# MainPowerSupply.net
KiCad netlist of a schematic drawn in Altium Designer
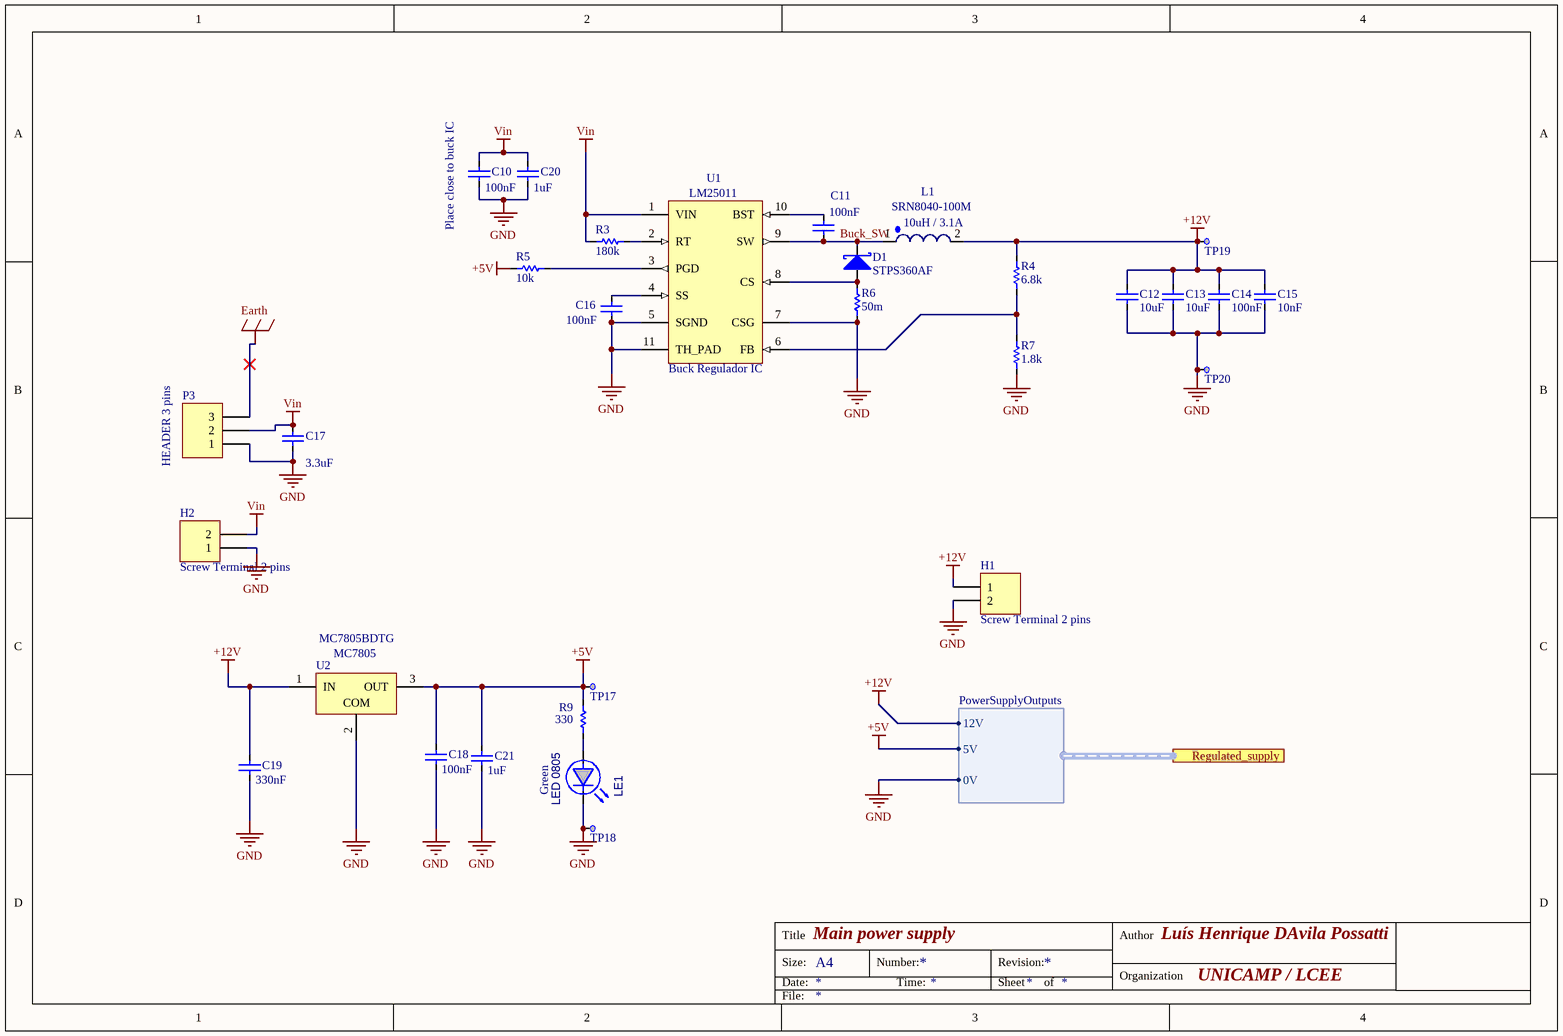
[diagram p0: MainPowerSupply.SchDoc]

(export (version "E")
  (design (tool "Eeschema 10.0.6"))
  (components
    (comp (ref "C10")
      (value "Place close to buck IC")
      (footprint "Capacitor 0805")
      (description "SMD ceramic capacitor 0805")
      (fields (field (name "ALTIUM_VALUE") "100nF"))
      (libsource (lib "EdgeInverter_library") (part "Capacitor 0805"))
    )
    (comp (ref "C11")
      (value "100nF")
      (footprint "Capacitor 0805")
      (description "SMD ceramic capacitor 0805")
      (fields (field (name "Comment") "Capacitor 0805"))
      (libsource (lib "EdgeInverter_library") (part "Capacitor 0805"))
    )
    (comp (ref "C12")
      (value "10uF")
      (footprint "Capacitor 0805")
      (description "SMD ceramic capacitor 0805")
      (fields (field (name "Comment") "Capacitor 0805"))
      (libsource (lib "EdgeInverter_library") (part "Capacitor 0805"))
    )
    (comp (ref "C13")
      (value "10uF")
      (footprint "Capacitor 0805")
      (description "SMD ceramic capacitor 0805")
      (fields (field (name "Comment") "Capacitor 0805"))
      (libsource (lib "EdgeInverter_library") (part "Capacitor 0805"))
    )
    (comp (ref "C14")
      (value "100nF")
      (footprint "Capacitor 0805")
      (description "SMD ceramic capacitor 0805")
      (fields (field (name "Comment") "Capacitor 0805"))
      (libsource (lib "EdgeInverter_library") (part "Capacitor 0805"))
    )
    (comp (ref "C15")
      (value "10nF")
      (footprint "Capacitor 0805")
      (description "SMD ceramic capacitor 0805")
      (fields (field (name "Comment") "Capacitor 0805"))
      (libsource (lib "EdgeInverter_library") (part "Capacitor 0805"))
    )
    (comp (ref "C16")
      (value "100nF")
      (footprint "Capacitor 0805")
      (description "SMD ceramic capacitor 0805")
      (fields (field (name "Comment") "Capacitor 0805"))
      (libsource (lib "EdgeInverter_library") (part "Capacitor 0805"))
    )
    (comp (ref "C17")
      (value "3.3uF")
      (footprint "Capacitor 0805")
      (description "SMD ceramic capacitor 0805")
      (fields (field (name "Comment") "Place close to input"))
      (libsource (lib "EdgeInverter_library") (part "Capacitor 0805"))
    )
    (comp (ref "C18")
      (value "100nF")
      (footprint "Capacitor 0805")
      (description "SMD ceramic capacitor 0805")
      (fields (field (name "Comment") "Place close do MC7805"))
      (libsource (lib "EdgeInverter_library") (part "Capacitor 0805"))
    )
    (comp (ref "C19")
      (value "330nF")
      (footprint "Capacitor 0805")
      (description "SMD ceramic capacitor 0805")
      (fields (field (name "Comment") "Place close do MC7805"))
      (libsource (lib "EdgeInverter_library") (part "Capacitor 0805"))
    )
    (comp (ref "C20")
      (value "1uF")
      (footprint "Capacitor 0805")
      (description "SMD ceramic capacitor 0805")
      (fields (field (name "Comment") "Place close to buck IC"))
      (libsource (lib "EdgeInverter_library") (part "Capacitor 0805"))
    )
    (comp (ref "C21")
      (value "1uF")
      (footprint "Capacitor 0805")
      (description "SMD ceramic capacitor 0805")
      (fields (field (name "Comment") "Place close do MC7805"))
      (libsource (lib "EdgeInverter_library") (part "Capacitor 0805"))
    )
    (comp (ref "D1")
      (value "STPS360AF")
      (footprint "SOD 128")
      (description "DIODE SCHOTTKY 60V 3A SOD128")
      (libsource (lib "EdgeInverter_library") (part "STPS360AF"))
    )
    (comp (ref "H1")
      (value "Screw Terminal 2 pins")
      (footprint "OSTTA020161")
      (libsource (lib "EdgeInverter_library") (part "OSTTA020161"))
    )
    (comp (ref "H2")
      (value "Screw Terminal 2 pins")
      (footprint "OSTTA020161")
      (libsource (lib "") (part "OSTTA020161_1"))
    )
    (comp (ref "L1")
      (value "SRN8040-100M")
      (footprint "SRN8040")
      (description "Inductor 10UH 3.1A 50 mΩ SMD")
      (fields (field (name "ALTIUM_VALUE") "10uH / 3.1A"))
      (libsource (lib "EdgeInverter_library") (part "SRN8040-100M"))
    )
    (comp (ref "LE1")
      (value "LED 0805")
      (footprint "LED 0805 Green")
      (description "LEDSMD 0805")
      (fields (field (name "COLOR") "Green"))
      (libsource (lib "EdgeInverter_library") (part "LEDSMD 0805"))
    )
    (comp (ref "P3")
      (value "HEADER 3 pins")
      (footprint "HDR1X3")
      (description "Header 2.54mm 3 pins")
      (libsource (lib "EdgeInverter_library") (part "HEADER 3 pins"))
    )
    (comp (ref "R3")
      (value "180k")
      (footprint "Resistor 0805")
      (description "SMD resistor 0805")
      (fields (field (name "Comment") "Resistor 0805"))
      (libsource (lib "EdgeInverter_library") (part "Resistor 0805"))
    )
    (comp (ref "R4")
      (value "6.8k")
      (footprint "Resistor 0805")
      (description "SMD resistor 0805")
      (fields (field (name "Comment") "Resistor 0805"))
      (libsource (lib "EdgeInverter_library") (part "Resistor 0805"))
    )
    (comp (ref "R5")
      (value "10k")
      (footprint "Resistor 0805")
      (description "SMD resistor 0805")
      (fields (field (name "Comment") "Resistor 0805"))
      (libsource (lib "EdgeInverter_library") (part "Resistor 0805"))
    )
    (comp (ref "R6")
      (value "50m")
      (footprint "Resistor 0805")
      (description "RESISTOR 0.05 OHM 1% 1W SMD 1206")
      (fields (field (name "Comment") "MCS1632R050FER"))
      (libsource (lib "EdgeInverter_library") (part "MCS1632R050FER"))
    )
    (comp (ref "R7")
      (value "1.8k")
      (footprint "Resistor 0805")
      (description "SMD resistor 0805")
      (fields (field (name "Comment") "Resistor 0805"))
      (libsource (lib "EdgeInverter_library") (part "Resistor 0805"))
    )
    (comp (ref "R9")
      (value "330")
      (footprint "Resistor 0805")
      (description "SMD resistor 0805")
      (fields (field (name "Comment") "Resistor 0805"))
      (libsource (lib "EdgeInverter_library") (part "Resistor 0805"))
    )
    (comp (ref "TP17")
      (value "Name of signal")
      (footprint "Test point")
      (description "Test point to probe with oscilloscope")
      (libsource (lib "EdgeInverter_library") (part "Test point"))
    )
    (comp (ref "TP18")
      (value "Name of signal")
      (footprint "Test point")
      (description "Test point to probe with oscilloscope")
      (libsource (lib "EdgeInverter_library") (part "Test point"))
    )
    (comp (ref "TP19")
      (value "Name of signal")
      (footprint "Test point")
      (description "Test point to probe with oscilloscope")
      (libsource (lib "EdgeInverter_library") (part "Test point"))
    )
    (comp (ref "TP20")
      (value "Name of signal")
      (footprint "Test point")
      (description "Test point to probe with oscilloscope")
      (libsource (lib "EdgeInverter_library") (part "Test point"))
    )
    (comp (ref "U1")
      (value "Buck Regulador IC")
      (footprint "HVSSOP 10")
      (description "IC REG BUCK ADJ 2A 10MSOP")
      (fields (field (name "ALTIUM_VALUE") "LM25011"))
      (libsource (lib "EdgeInverter_library") (part "LM25011"))
    )
    (comp (ref "U2")
      (value "MC7805BDTG")
      (footprint "DPAK-3")
      (description "IC REG LINEAR 5V 1A DPAK-3")
      (fields (field (name "ALTIUM_VALUE") "MC7805"))
      (libsource (lib "EdgeInverter_library") (part "MC7805BDTG"))
    )
  )
  (nets
    (net (code "2") (name "+5V") (class "Default")
      (node (ref "C18") (pin "1") (pinfunction "1_1") (pintype "passive"))
      (node (ref "C21") (pin "1") (pinfunction "1_1") (pintype "passive"))
      (node (ref "R5") (pin "1") (pinfunction "1_1") (pintype "passive"))
      (node (ref "R9") (pin "2") (pinfunction "2_2") (pintype "passive"))
      (node (ref "TP17") (pin "1") (pinfunction "1_1") (pintype "passive"))
      (node (ref "U2") (pin "3") (pinfunction "OUT_3") (pintype "power_in"))
    )
    (net (code "3") (name "+12V") (class "Default")
      (node (ref "C12") (pin "1") (pinfunction "1_1") (pintype "passive"))
      (node (ref "C13") (pin "1") (pinfunction "1_1") (pintype "passive"))
      (node (ref "C14") (pin "1") (pinfunction "1_1") (pintype "passive"))
      (node (ref "C15") (pin "1") (pinfunction "1_1") (pintype "passive"))
      (node (ref "C19") (pin "1") (pinfunction "1_1") (pintype "passive"))
      (node (ref "H1") (pin "1") (pinfunction "1_1") (pintype "passive"))
      (node (ref "L1") (pin "2") (pinfunction "2_2") (pintype "passive"))
      (node (ref "R4") (pin "2") (pinfunction "2_2") (pintype "passive"))
      (node (ref "TP19") (pin "1") (pinfunction "1_1") (pintype "passive"))
      (node (ref "U2") (pin "1") (pinfunction "IN_1") (pintype "power_in"))
    )
    (net (code "4") (name "/Buck_SW") (class "Default")
      (node (ref "C11") (pin "2") (pinfunction "2_2") (pintype "passive"))
      (node (ref "D1") (pin "2") (pinfunction "K_2") (pintype "passive"))
      (node (ref "L1") (pin "1") (pinfunction "1_1") (pintype "passive"))
      (node (ref "U1") (pin "9") (pinfunction "SW_9") (pintype "output"))
    )
    (net (code "6") (name "Earth") (class "Default")
      (node (ref "P3") (pin "3") (pinfunction "3_3") (pintype "passive"))
    )
    (net (code "7") (name "GND") (class "Default")
      (node (ref "C10") (pin "2") (pinfunction "2_2") (pintype "passive"))
      (node (ref "C12") (pin "2") (pinfunction "2_2") (pintype "passive"))
      (node (ref "C13") (pin "2") (pinfunction "2_2") (pintype "passive"))
      (node (ref "C14") (pin "2") (pinfunction "2_2") (pintype "passive"))
      (node (ref "C15") (pin "2") (pinfunction "2_2") (pintype "passive"))
      (node (ref "C16") (pin "2") (pinfunction "2_2") (pintype "passive"))
      (node (ref "C17") (pin "2") (pinfunction "2_2") (pintype "passive"))
      (node (ref "C18") (pin "2") (pinfunction "2_2") (pintype "passive"))
      (node (ref "C19") (pin "2") (pinfunction "2_2") (pintype "passive"))
      (node (ref "C20") (pin "2") (pinfunction "2_2") (pintype "passive"))
      (node (ref "C21") (pin "2") (pinfunction "2_2") (pintype "passive"))
      (node (ref "H1") (pin "2") (pinfunction "2_2") (pintype "passive"))
      (node (ref "H2") (pin "1") (pinfunction "1_1") (pintype "passive"))
      (node (ref "LE1") (pin "2") (pinfunction "2_2") (pintype "passive"))
      (node (ref "P3") (pin "1") (pinfunction "1_1") (pintype "passive"))
      (node (ref "R6") (pin "1") (pinfunction "1_1") (pintype "passive"))
      (node (ref "R7") (pin "1") (pinfunction "1_1") (pintype "passive"))
      (node (ref "TP18") (pin "1") (pinfunction "1_1") (pintype "passive"))
      (node (ref "TP20") (pin "1") (pinfunction "1_1") (pintype "passive"))
      (node (ref "U1") (pin "11") (pinfunction "TH_PAD_11") (pintype "power_in"))
      (node (ref "U1") (pin "5") (pinfunction "SGND_5") (pintype "power_in"))
      (node (ref "U1") (pin "7") (pinfunction "CSG_7") (pintype "power_in"))
      (node (ref "U2") (pin "2") (pinfunction "COM_2") (pintype "power_in"))
    )
    (net (code "8") (name "Net-(D1-A)") (class "Default")
      (node (ref "D1") (pin "1") (pinfunction "A_1") (pintype "passive"))
      (node (ref "R6") (pin "2") (pinfunction "2_2") (pintype "passive"))
      (node (ref "U1") (pin "8") (pinfunction "CS_8") (pintype "input"))
    )
    (net (code "9") (name "Net-(LE1-Pad1)") (class "Default")
      (node (ref "LE1") (pin "1") (pinfunction "1_1") (pintype "passive"))
      (node (ref "R9") (pin "1") (pinfunction "1_1") (pintype "passive"))
    )
    (net (code "10") (name "Net-(U1-BST)") (class "Default")
      (node (ref "C11") (pin "1") (pinfunction "1_1") (pintype "passive"))
      (node (ref "U1") (pin "10") (pinfunction "BST_10") (pintype "input"))
    )
    (net (code "11") (name "Net-(U1-FB)") (class "Default")
      (node (ref "R4") (pin "1") (pinfunction "1_1") (pintype "passive"))
      (node (ref "R7") (pin "2") (pinfunction "2_2") (pintype "passive"))
      (node (ref "U1") (pin "6") (pinfunction "FB_6") (pintype "input"))
    )
    (net (code "12") (name "Net-(U1-PGD)") (class "Default")
      (node (ref "R5") (pin "2") (pinfunction "2_2") (pintype "passive"))
      (node (ref "U1") (pin "3") (pinfunction "PGD_3") (pintype "output"))
    )
    (net (code "13") (name "Net-(U1-RT)") (class "Default")
      (node (ref "R3") (pin "2") (pinfunction "2_2") (pintype "passive"))
      (node (ref "U1") (pin "2") (pinfunction "RT_2") (pintype "input"))
    )
    (net (code "14") (name "Net-(U1-SS)") (class "Default")
      (node (ref "C16") (pin "1") (pinfunction "1_1") (pintype "passive"))
      (node (ref "U1") (pin "4") (pinfunction "SS_4") (pintype "input"))
    )
    (net (code "15") (name "Vin") (class "Default")
      (node (ref "C10") (pin "1") (pinfunction "1_1") (pintype "passive"))
      (node (ref "C17") (pin "1") (pinfunction "1_1") (pintype "passive"))
      (node (ref "C20") (pin "1") (pinfunction "1_1") (pintype "passive"))
      (node (ref "H2") (pin "2") (pinfunction "2_2") (pintype "passive"))
      (node (ref "P3") (pin "2") (pinfunction "2_2") (pintype "passive"))
      (node (ref "R3") (pin "1") (pinfunction "1_1") (pintype "passive"))
      (node (ref "U1") (pin "1") (pinfunction "VIN_1") (pintype "power_in"))
    )
  )
)
